# FPGA_PWR.net
KiCad netlist of a schematic drawn in Altium Designer
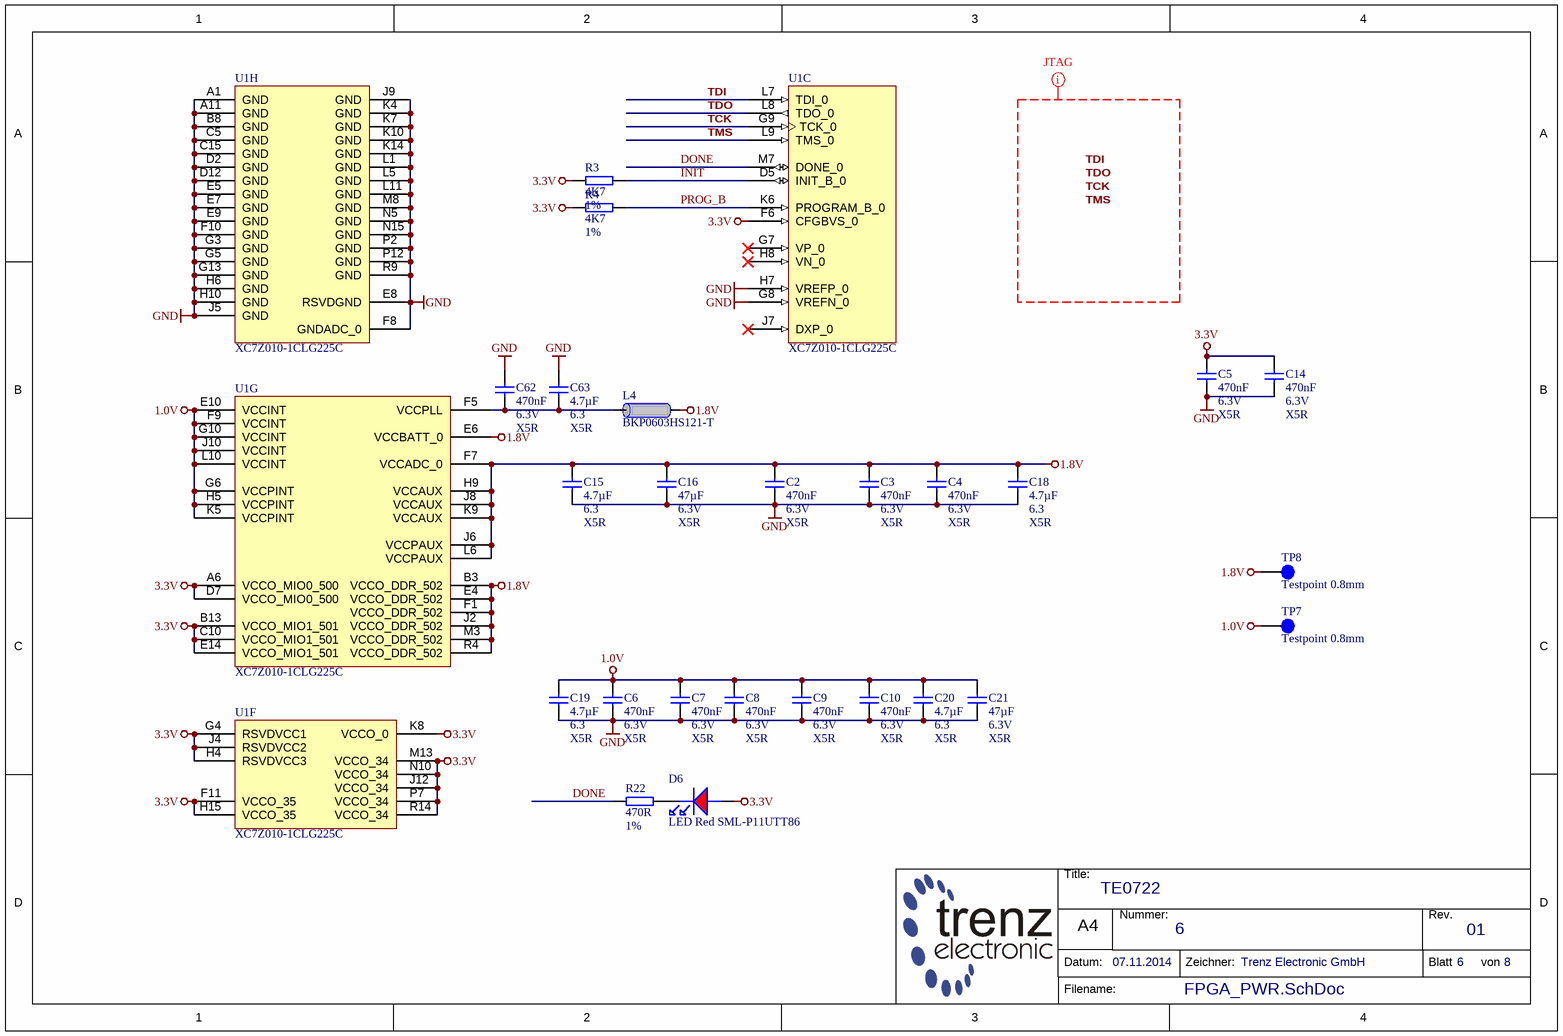
[diagram p0: FPGA_PWR.SchDoc]

(export (version "E")
  (design (tool "Eeschema 10.0.6"))
  (components
    (comp (ref "C2")
      (value "470nF")
      (footprint "CAPC0603X33N")
      (description "KON 470nF X5R 6.3V SMD 20%")
      (fields
        (field (name "VOLTAGE") "6.3V")
        (field (name "TECHNOLOGY") "X5R")
        (field (name "TOLERANCE") "20%")
      )
      (libsource (lib "TE") (part "CAP-NP"))
    )
    (comp (ref "C3")
      (value "470nF")
      (footprint "CAPC0603X33N")
      (description "KON 470nF X5R 6.3V SMD 20%")
      (fields
        (field (name "VOLTAGE") "6.3V")
        (field (name "TECHNOLOGY") "X5R")
        (field (name "TOLERANCE") "20%")
      )
      (libsource (lib "TE") (part "CAP-NP"))
    )
    (comp (ref "C4")
      (value "470nF")
      (footprint "CAPC0603X33N")
      (description "KON 470nF X5R 6.3V SMD 20%")
      (fields
        (field (name "VOLTAGE") "6.3V")
        (field (name "TECHNOLOGY") "X5R")
        (field (name "TOLERANCE") "20%")
      )
      (libsource (lib "TE") (part "CAP-NP"))
    )
    (comp (ref "C5")
      (value "470nF")
      (footprint "CAPC0603X33N")
      (description "KON 470nF X5R 6.3V SMD 20%")
      (fields
        (field (name "VOLTAGE") "6.3V")
        (field (name "TECHNOLOGY") "X5R")
        (field (name "TOLERANCE") "20%")
      )
      (libsource (lib "TE") (part "CAP-NP"))
    )
    (comp (ref "C6")
      (value "470nF")
      (footprint "CAPC0603X33N")
      (description "KON 470nF X5R 6.3V SMD 20%")
      (fields
        (field (name "VOLTAGE") "6.3V")
        (field (name "TECHNOLOGY") "X5R")
        (field (name "TOLERANCE") "20%")
      )
      (libsource (lib "TE") (part "CAP-NP"))
    )
    (comp (ref "C7")
      (value "470nF")
      (footprint "CAPC0603X33N")
      (description "KON 470nF X5R 6.3V SMD 20%")
      (fields
        (field (name "VOLTAGE") "6.3V")
        (field (name "TECHNOLOGY") "X5R")
        (field (name "TOLERANCE") "20%")
      )
      (libsource (lib "TE") (part "CAP-NP"))
    )
    (comp (ref "C8")
      (value "470nF")
      (footprint "CAPC0603X33N")
      (description "KON 470nF X5R 6.3V SMD 20%")
      (fields
        (field (name "VOLTAGE") "6.3V")
        (field (name "TECHNOLOGY") "X5R")
        (field (name "TOLERANCE") "20%")
      )
      (libsource (lib "TE") (part "CAP-NP"))
    )
    (comp (ref "C9")
      (value "470nF")
      (footprint "CAPC0603X33N")
      (description "KON 470nF X5R 6.3V SMD 20%")
      (fields
        (field (name "VOLTAGE") "6.3V")
        (field (name "TECHNOLOGY") "X5R")
        (field (name "TOLERANCE") "20%")
      )
      (libsource (lib "TE") (part "CAP-NP"))
    )
    (comp (ref "C10")
      (value "470nF")
      (footprint "CAPC0603X33N")
      (description "KON 470nF X5R 6.3V SMD 20%")
      (fields
        (field (name "VOLTAGE") "6.3V")
        (field (name "TECHNOLOGY") "X5R")
        (field (name "TOLERANCE") "20%")
      )
      (libsource (lib "TE") (part "CAP-NP"))
    )
    (comp (ref "C14")
      (value "470nF")
      (footprint "CAPC0603X33N")
      (description "KON 470nF X5R 6.3V SMD 20%")
      (fields
        (field (name "VOLTAGE") "6.3V")
        (field (name "TECHNOLOGY") "X5R")
        (field (name "TOLERANCE") "20%")
      )
      (libsource (lib "TE") (part "CAP-NP"))
    )
    (comp (ref "C15")
      (value "4.7µF")
      (footprint "CAPC1005X60N")
      (description "KON 4.7µF 6.3V X5R SMD 20%")
      (fields
        (field (name "VOLTAGE") "6.3")
        (field (name "TECHNOLOGY") "X5R")
        (field (name "TOLERANCE") "20%")
      )
      (libsource (lib "TE") (part "CAP-NP"))
    )
    (comp (ref "C16")
      (value "47µF")
      (footprint "CAPC2012X135N")
      (description "KON 47µF 6,3V  X5R SMD 20%")
      (fields
        (field (name "VOLTAGE") "6.3V")
        (field (name "TECHNOLOGY") "X5R")
        (field (name "TOLERANCE") "20%")
      )
      (libsource (lib "TE") (part "CAP-NP"))
    )
    (comp (ref "C18")
      (value "4.7µF")
      (footprint "CAPC1005X60N")
      (description "KON 4.7µF 6.3V X5R SMD 20%")
      (fields
        (field (name "VOLTAGE") "6.3")
        (field (name "TECHNOLOGY") "X5R")
        (field (name "TOLERANCE") "20%")
      )
      (libsource (lib "TE") (part "CAP-NP"))
    )
    (comp (ref "C19")
      (value "4.7µF")
      (footprint "CAPC1005X60N")
      (description "KON 4.7µF 6.3V X5R SMD 20%")
      (fields
        (field (name "VOLTAGE") "6.3")
        (field (name "TECHNOLOGY") "X5R")
        (field (name "TOLERANCE") "20%")
      )
      (libsource (lib "TE") (part "CAP-NP"))
    )
    (comp (ref "C20")
      (value "4.7µF")
      (footprint "CAPC1005X60N")
      (description "KON 4.7µF 6.3V X5R SMD 20%")
      (fields
        (field (name "VOLTAGE") "6.3")
        (field (name "TECHNOLOGY") "X5R")
        (field (name "TOLERANCE") "20%")
      )
      (libsource (lib "TE") (part "CAP-NP"))
    )
    (comp (ref "C21")
      (value "47µF")
      (footprint "CAPC2012X135N")
      (description "KON 47µF 6,3V  X5R SMD 20%")
      (fields
        (field (name "VOLTAGE") "6.3V")
        (field (name "TECHNOLOGY") "X5R")
        (field (name "TOLERANCE") "20%")
      )
      (libsource (lib "TE") (part "CAP-NP"))
    )
    (comp (ref "C62")
      (value "470nF")
      (footprint "CAPC0603X33N")
      (description "KON 470nF X5R 6.3V SMD 20%")
      (fields
        (field (name "VOLTAGE") "6.3V")
        (field (name "TECHNOLOGY") "X5R")
        (field (name "TOLERANCE") "20%")
      )
      (libsource (lib "TE") (part "CAP-NP"))
    )
    (comp (ref "C63")
      (value "4.7µF")
      (footprint "CAPC1005X60N")
      (description "KON 4.7µF 6.3V X5R SMD 20%")
      (fields
        (field (name "VOLTAGE") "6.3")
        (field (name "TECHNOLOGY") "X5R")
        (field (name "TOLERANCE") "20%")
      )
      (libsource (lib "TE") (part "CAP-NP"))
    )
    (comp (ref "D6")
      (value "LED Red SML-P11UTT86")
      (footprint "LEDC1006X25N_RED")
      (description "LED Rot SML-P11UTT86 SMD")
      (libsource (lib "TE") (part "LED_ROT"))
    )
    (comp (ref "L4")
      (value "BKP0603HS121-T")
      (footprint "INDC0603X33N")
      (description "Ferritdurchführung SMD 0201")
      (fields (field (name "TOLERANCE") "25%"))
      (libsource (lib "TE") (part "Ferritperle"))
    )
    (comp (ref "R3")
      (value "4K7")
      (footprint "RESC0603X26N")
      (description "WID SMD 4K7 1% 0,05W")
      (fields (field (name "TOLERANCE") "1%"))
      (libsource (lib "TE") (part "RES"))
    )
    (comp (ref "R4")
      (value "4K7")
      (footprint "RESC0603X26N")
      (description "WID SMD 4K7 1% 0,05W")
      (fields (field (name "TOLERANCE") "1%"))
      (libsource (lib "TE") (part "RES"))
    )
    (comp (ref "R22")
      (value "470R")
      (footprint "RESC1005X40N")
      (description "WID SMD 470R 1% 0,063W")
      (fields (field (name "TOLERANCE") "1%"))
      (libsource (lib "TE") (part "RES"))
    )
    (comp (ref "TP7") (value "Testpoint 0.8mm") (footprint "TP_0.8mm") (libsource (lib "TE") (part "TP")))
    (comp (ref "TP8") (value "Testpoint 0.8mm") (footprint "TP_0.8mm") (libsource (lib "TE") (part "TP")))
    (comp (ref "U1")
      (value "XC7Z010-1CLG225C")
      (footprint "CLG225")
      (libsource (lib "TE") (part "XC7Z010-CLG225"))
    )
  )
  (nets
    (net (code "1") (name "/DONE") (class "Default")
      (node (ref "R22") (pin "2") (pinfunction "2_2") (pintype "passive"))
      (node (ref "U1") (pin "M7") (pinfunction "DONE_0_M7") (pintype "bidirectional"))
    )
    (net (code "2") (name "/INIT") (class "Default")
      (node (ref "R3") (pin "1") (pinfunction "1_1") (pintype "passive"))
      (node (ref "U1") (pin "D5") (pinfunction "INIT_B_0_D5") (pintype "bidirectional"))
    )
    (net (code "3") (name "/PROG_B") (class "Default")
      (node (ref "R4") (pin "1") (pinfunction "1_1") (pintype "passive"))
      (node (ref "U1") (pin "K6") (pinfunction "PROGRAM_B_0_K6") (pintype "input"))
    )
    (net (code "4") (name "/TCK") (class "Default")
      (node (ref "U1") (pin "G9") (pinfunction "TCK_0_G9") (pintype "input"))
    )
    (net (code "5") (name "/TDI") (class "Default")
      (node (ref "U1") (pin "L7") (pinfunction "TDI_0_L7") (pintype "input"))
    )
    (net (code "6") (name "/TDO") (class "Default")
      (node (ref "U1") (pin "L8") (pinfunction "TDO_0_L8") (pintype "output"))
    )
    (net (code "7") (name "/TMS") (class "Default")
      (node (ref "U1") (pin "L9") (pinfunction "TMS_0_L9") (pintype "input"))
    )
    (net (code "8") (name "1.0V") (class "Default")
      (node (ref "C10") (pin "2") (pinfunction "2_2") (pintype "passive"))
      (node (ref "C19") (pin "1") (pinfunction "1_1") (pintype "passive"))
      (node (ref "C20") (pin "1") (pinfunction "1_1") (pintype "passive"))
      (node (ref "C21") (pin "1") (pinfunction "1_1") (pintype "passive"))
      (node (ref "C6") (pin "2") (pinfunction "2_2") (pintype "passive"))
      (node (ref "C7") (pin "2") (pinfunction "2_2") (pintype "passive"))
      (node (ref "C8") (pin "2") (pinfunction "2_2") (pintype "passive"))
      (node (ref "C9") (pin "2") (pinfunction "2_2") (pintype "passive"))
      (node (ref "TP7") (pin "1") (pintype "passive"))
      (node (ref "U1") (pin "E10") (pinfunction "VCCINT_E10") (pintype "power_in"))
      (node (ref "U1") (pin "F9") (pinfunction "VCCINT_F9") (pintype "power_in"))
      (node (ref "U1") (pin "G10") (pinfunction "VCCINT_G10") (pintype "power_in"))
      (node (ref "U1") (pin "G6") (pinfunction "VCCPINT_G6") (pintype "power_in"))
      (node (ref "U1") (pin "H5") (pinfunction "VCCPINT_H5") (pintype "power_in"))
      (node (ref "U1") (pin "J10") (pinfunction "VCCINT_J10") (pintype "power_in"))
      (node (ref "U1") (pin "K5") (pinfunction "VCCPINT_K5") (pintype "power_in"))
      (node (ref "U1") (pin "L10") (pinfunction "VCCINT_L10") (pintype "power_in"))
    )
    (net (code "9") (name "1.8V") (class "Default")
      (node (ref "C15") (pin "1") (pinfunction "1_1") (pintype "passive"))
      (node (ref "C16") (pin "1") (pinfunction "1_1") (pintype "passive"))
      (node (ref "C18") (pin "1") (pinfunction "1_1") (pintype "passive"))
      (node (ref "C2") (pin "2") (pinfunction "2_2") (pintype "passive"))
      (node (ref "C3") (pin "1") (pinfunction "1_1") (pintype "passive"))
      (node (ref "C4") (pin "2") (pinfunction "2_2") (pintype "passive"))
      (node (ref "L4") (pin "1") (pinfunction "1_1") (pintype "passive"))
      (node (ref "TP8") (pin "1") (pintype "passive"))
      (node (ref "U1") (pin "B3") (pinfunction "VCCO_DDR_502_B3") (pintype "power_in"))
      (node (ref "U1") (pin "E4") (pinfunction "VCCO_DDR_502_E4") (pintype "power_in"))
      (node (ref "U1") (pin "E6") (pinfunction "VCCBATT_0_E6") (pintype "power_in"))
      (node (ref "U1") (pin "F1") (pinfunction "VCCO_DDR_502_F1") (pintype "power_in"))
      (node (ref "U1") (pin "F7") (pinfunction "VCCADC_0_F7") (pintype "power_in"))
      (node (ref "U1") (pin "H9") (pinfunction "VCCAUX_H9") (pintype "power_in"))
      (node (ref "U1") (pin "J2") (pinfunction "VCCO_DDR_502_J2") (pintype "power_in"))
      (node (ref "U1") (pin "J6") (pinfunction "VCCPAUX_J6") (pintype "power_in"))
      (node (ref "U1") (pin "J8") (pinfunction "VCCAUX_J8") (pintype "power_in"))
      (node (ref "U1") (pin "K9") (pinfunction "VCCAUX_K9") (pintype "power_in"))
      (node (ref "U1") (pin "L6") (pinfunction "VCCPAUX_L6") (pintype "power_in"))
      (node (ref "U1") (pin "M3") (pinfunction "VCCO_DDR_502_M3") (pintype "power_in"))
      (node (ref "U1") (pin "R4") (pinfunction "VCCO_DDR_502_R4") (pintype "power_in"))
    )
    (net (code "10") (name "3.3V") (class "Default")
      (node (ref "C14") (pin "2") (pinfunction "2_2") (pintype "passive"))
      (node (ref "C5") (pin "2") (pinfunction "2_2") (pintype "passive"))
      (node (ref "D6") (pin "A") (pinfunction "A_A") (pintype "passive"))
      (node (ref "R3") (pin "2") (pinfunction "2_2") (pintype "passive"))
      (node (ref "R4") (pin "2") (pinfunction "2_2") (pintype "passive"))
      (node (ref "U1") (pin "A6") (pinfunction "VCCO_MIO0_500_A6") (pintype "power_in"))
      (node (ref "U1") (pin "B13") (pinfunction "VCCO_MIO1_501_B13") (pintype "power_in"))
      (node (ref "U1") (pin "C10") (pinfunction "VCCO_MIO1_501_C10") (pintype "power_in"))
      (node (ref "U1") (pin "D7") (pinfunction "VCCO_MIO0_500_D7") (pintype "power_in"))
      (node (ref "U1") (pin "E14") (pinfunction "VCCO_MIO1_501_E14") (pintype "power_in"))
      (node (ref "U1") (pin "F11") (pinfunction "VCCO_35_F11") (pintype "power_in"))
      (node (ref "U1") (pin "F6") (pinfunction "CFGBVS_0_F6") (pintype "input"))
      (node (ref "U1") (pin "G4") (pinfunction "RSVDVCC1_G4") (pintype "power_in"))
      (node (ref "U1") (pin "H15") (pinfunction "VCCO_35_H15") (pintype "power_in"))
      (node (ref "U1") (pin "H4") (pinfunction "RSVDVCC3_H4") (pintype "power_in"))
      (node (ref "U1") (pin "J12") (pinfunction "VCCO_34_J12") (pintype "power_in"))
      (node (ref "U1") (pin "J4") (pinfunction "RSVDVCC2_J4") (pintype "power_in"))
      (node (ref "U1") (pin "K8") (pinfunction "VCCO_0_K8") (pintype "power_in"))
      (node (ref "U1") (pin "M13") (pinfunction "VCCO_34_M13") (pintype "power_in"))
      (node (ref "U1") (pin "N10") (pinfunction "VCCO_34_N10") (pintype "power_in"))
      (node (ref "U1") (pin "P7") (pinfunction "VCCO_34_P7") (pintype "power_in"))
      (node (ref "U1") (pin "R14") (pinfunction "VCCO_34_R14") (pintype "power_in"))
    )
    (net (code "11") (name "GND") (class "Default")
      (node (ref "C10") (pin "1") (pinfunction "1_1") (pintype "passive"))
      (node (ref "C14") (pin "1") (pinfunction "1_1") (pintype "passive"))
      (node (ref "C15") (pin "2") (pinfunction "2_2") (pintype "passive"))
      (node (ref "C16") (pin "2") (pinfunction "2_2") (pintype "passive"))
      (node (ref "C18") (pin "2") (pinfunction "2_2") (pintype "passive"))
      (node (ref "C19") (pin "2") (pinfunction "2_2") (pintype "passive"))
      (node (ref "C2") (pin "1") (pinfunction "1_1") (pintype "passive"))
      (node (ref "C20") (pin "2") (pinfunction "2_2") (pintype "passive"))
      (node (ref "C21") (pin "2") (pinfunction "2_2") (pintype "passive"))
      (node (ref "C3") (pin "2") (pinfunction "2_2") (pintype "passive"))
      (node (ref "C4") (pin "1") (pinfunction "1_1") (pintype "passive"))
      (node (ref "C5") (pin "1") (pinfunction "1_1") (pintype "passive"))
      (node (ref "C6") (pin "1") (pinfunction "1_1") (pintype "passive"))
      (node (ref "C62") (pin "1") (pinfunction "1_1") (pintype "passive"))
      (node (ref "C63") (pin "1") (pinfunction "1_1") (pintype "passive"))
      (node (ref "C7") (pin "1") (pinfunction "1_1") (pintype "passive"))
      (node (ref "C8") (pin "1") (pinfunction "1_1") (pintype "passive"))
      (node (ref "C9") (pin "1") (pinfunction "1_1") (pintype "passive"))
      (node (ref "U1") (pin "A1") (pinfunction "GND_A1") (pintype "power_in"))
      (node (ref "U1") (pin "A11") (pinfunction "GND_A11") (pintype "power_in"))
      (node (ref "U1") (pin "B8") (pinfunction "GND_B8") (pintype "power_in"))
      (node (ref "U1") (pin "C15") (pinfunction "GND_C15") (pintype "power_in"))
      (node (ref "U1") (pin "C5") (pinfunction "GND_C5") (pintype "power_in"))
      (node (ref "U1") (pin "D12") (pinfunction "GND_D12") (pintype "power_in"))
      (node (ref "U1") (pin "D2") (pinfunction "GND_D2") (pintype "power_in"))
      (node (ref "U1") (pin "E5") (pinfunction "GND_E5") (pintype "power_in"))
      (node (ref "U1") (pin "E7") (pinfunction "GND_E7") (pintype "power_in"))
      (node (ref "U1") (pin "E8") (pinfunction "RSVDGND_E8") (pintype "power_in"))
      (node (ref "U1") (pin "E9") (pinfunction "GND_E9") (pintype "power_in"))
      (node (ref "U1") (pin "F10") (pinfunction "GND_F10") (pintype "power_in"))
      (node (ref "U1") (pin "F8") (pinfunction "GNDADC_0_F8") (pintype "power_in"))
      (node (ref "U1") (pin "G13") (pinfunction "GND_G13") (pintype "power_in"))
      (node (ref "U1") (pin "G3") (pinfunction "GND_G3") (pintype "power_in"))
      (node (ref "U1") (pin "G5") (pinfunction "GND_G5") (pintype "power_in"))
      (node (ref "U1") (pin "G8") (pinfunction "VREFN_0_G8") (pintype "input"))
      (node (ref "U1") (pin "H10") (pinfunction "GND_H10") (pintype "power_in"))
      (node (ref "U1") (pin "H6") (pinfunction "GND_H6") (pintype "power_in"))
      (node (ref "U1") (pin "H7") (pinfunction "VREFP_0_H7") (pintype "input"))
      (node (ref "U1") (pin "J5") (pinfunction "GND_J5") (pintype "power_in"))
      (node (ref "U1") (pin "J9") (pinfunction "GND_J9") (pintype "power_in"))
      (node (ref "U1") (pin "K10") (pinfunction "GND_K10") (pintype "power_in"))
      (node (ref "U1") (pin "K14") (pinfunction "GND_K14") (pintype "power_in"))
      (node (ref "U1") (pin "K4") (pinfunction "GND_K4") (pintype "power_in"))
      (node (ref "U1") (pin "K7") (pinfunction "GND_K7") (pintype "power_in"))
      (node (ref "U1") (pin "L1") (pinfunction "GND_L1") (pintype "power_in"))
      (node (ref "U1") (pin "L11") (pinfunction "GND_L11") (pintype "power_in"))
      (node (ref "U1") (pin "L5") (pinfunction "GND_L5") (pintype "power_in"))
      (node (ref "U1") (pin "M8") (pinfunction "GND_M8") (pintype "power_in"))
      (node (ref "U1") (pin "N15") (pinfunction "GND_N15") (pintype "power_in"))
      (node (ref "U1") (pin "N5") (pinfunction "GND_N5") (pintype "power_in"))
      (node (ref "U1") (pin "P12") (pinfunction "GND_P12") (pintype "power_in"))
      (node (ref "U1") (pin "P2") (pinfunction "GND_P2") (pintype "power_in"))
      (node (ref "U1") (pin "R9") (pinfunction "GND_R9") (pintype "power_in"))
    )
    (net (code "12") (name "Net-(D6-PadK)") (class "Default")
      (node (ref "D6") (pin "K") (pinfunction "K_K") (pintype "passive"))
      (node (ref "R22") (pin "1") (pinfunction "1_1") (pintype "passive"))
    )
    (net (code "13") (name "Net-(U1G-VCCPLL)") (class "Default")
      (node (ref "C62") (pin "2") (pinfunction "2_2") (pintype "passive"))
      (node (ref "C63") (pin "2") (pinfunction "2_2") (pintype "passive"))
      (node (ref "L4") (pin "2") (pinfunction "2_2") (pintype "passive"))
      (node (ref "U1") (pin "F5") (pinfunction "VCCPLL_F5") (pintype "power_in"))
    )
    (net (code "14") (name "unconnected-(U1C-DXP_0-PadJ7)") (class "Default")
      (node (ref "U1") (pin "J7") (pinfunction "DXP_0_J7") (pintype "input+no_connect"))
    )
    (net (code "15") (name "unconnected-(U1C-VN_0-PadH8)") (class "Default")
      (node (ref "U1") (pin "H8") (pinfunction "VN_0_H8") (pintype "input+no_connect"))
    )
    (net (code "16") (name "unconnected-(U1C-VP_0-PadG7)") (class "Default")
      (node (ref "U1") (pin "G7") (pinfunction "VP_0_G7") (pintype "input+no_connect"))
    )
  )
)
